# FAB_FTDI.net
KiCad netlist of a schematic drawn in EAGLE
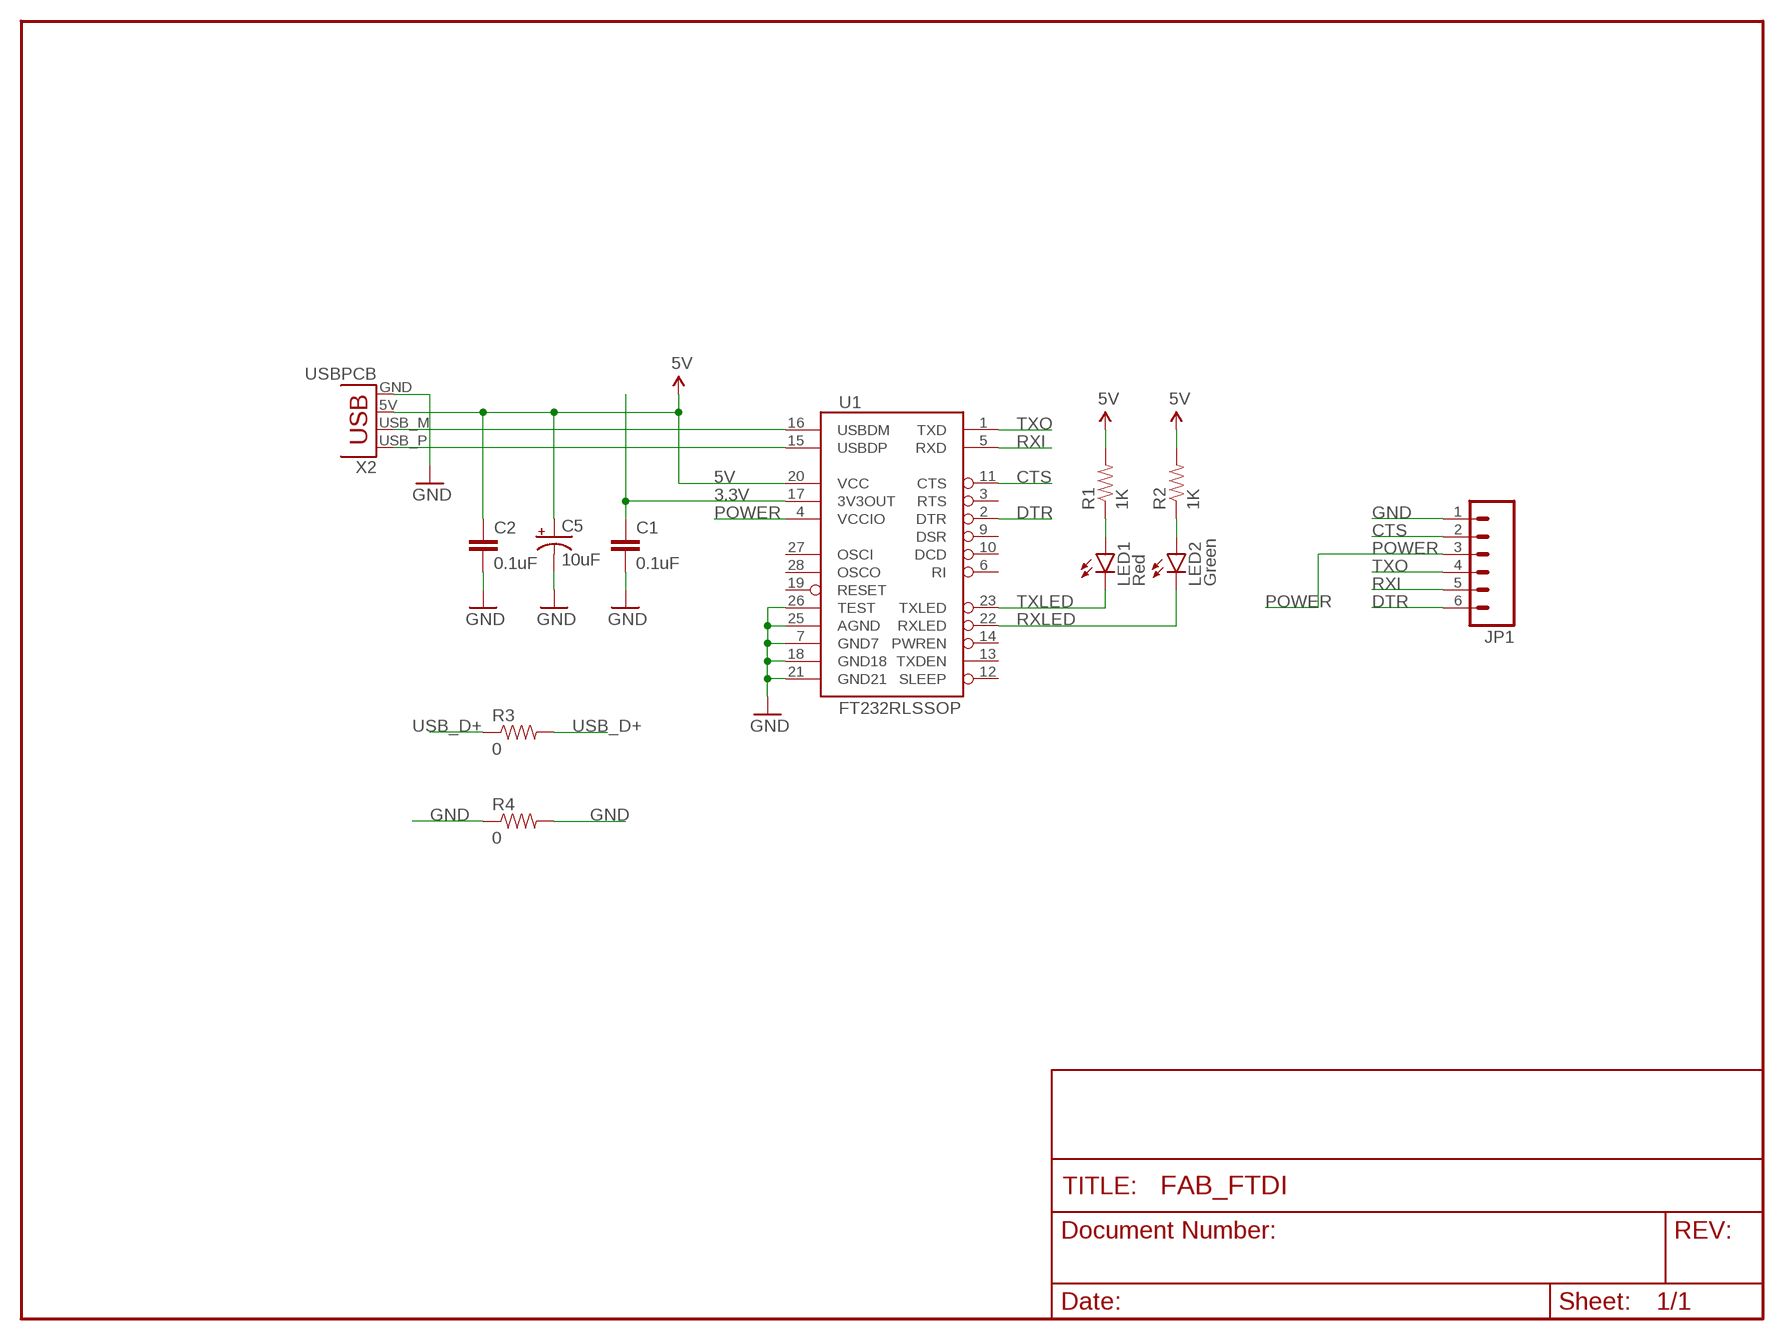
[diagram p0: schematic, sheet 1]

(export (version "E")
  (design (tool "Eeschema 10.0.6"))
  (components
    (comp (ref "C1")
      (value "0.1uF")
      (footprint "eagle-import:1206")
      (libsource (lib "eagle-import") (part "CAP1206"))
    )
    (comp (ref "C2")
      (value "0.1uF")
      (footprint "eagle-import:1206")
      (libsource (lib "eagle-import") (part "CAP1206"))
    )
    (comp (ref "C5")
      (value "10uF")
      (footprint "eagle-import:EIA3216")
      (libsource (lib "eagle-import") (part "CAP_POL1206"))
    )
    (comp (ref "JP1")
      (value "M06SMD-FEMALE-V2")
      (footprint "eagle-import:1X06-SMD-FEMALE-V2")
      (libsource (lib "eagle-import") (part "M06SMD-FEMALE-V2"))
    )
    (comp (ref "LED1")
      (value "Red")
      (footprint "eagle-import:LED-1206")
      (libsource (lib "eagle-import") (part "LED1206"))
    )
    (comp (ref "LED2")
      (value "Green")
      (footprint "eagle-import:LED-1206")
      (libsource (lib "eagle-import") (part "LED1206"))
    )
    (comp (ref "R1")
      (value "1K")
      (footprint "eagle-import:1206")
      (libsource (lib "eagle-import") (part "RESISTOR1206"))
    )
    (comp (ref "R2")
      (value "1K")
      (footprint "eagle-import:1206")
      (libsource (lib "eagle-import") (part "RESISTOR1206"))
    )
    (comp (ref "R3")
      (value "0")
      (footprint "eagle-import:1206")
      (libsource (lib "eagle-import") (part "RESISTOR1206"))
    )
    (comp (ref "R4")
      (value "0")
      (footprint "eagle-import:1206")
      (libsource (lib "eagle-import") (part "RESISTOR1206"))
    )
    (comp (ref "U1")
      (value "FT232RLSSOP")
      (footprint "eagle-import:SSOP28DB")
      (libsource (lib "eagle-import") (part "FT232RLSSOP"))
    )
    (comp (ref "X2")
      (value "USBPCB")
      (footprint "eagle-import:USB-A-PCB")
      (libsource (lib "eagle-import") (part "USBPCB"))
    )
  )
  (nets
    (net (code "1") (name "/3.3V") (class "Default")
      (node (ref "C1") (pin "1") (pinfunction "1_1") (pintype "passive"))
      (node (ref "U1") (pin "17") (pinfunction "3V3OUT_17") (pintype "output"))
    )
    (net (code "2") (name "/CTS") (class "Default")
      (node (ref "JP1") (pin "2") (pinfunction "2_2") (pintype "passive"))
      (node (ref "U1") (pin "11") (pinfunction "CTS_11") (pintype "input"))
    )
    (net (code "3") (name "/DTR") (class "Default")
      (node (ref "JP1") (pin "6") (pinfunction "6_6") (pintype "passive"))
      (node (ref "U1") (pin "2") (pinfunction "DTR_2") (pintype "output"))
    )
    (net (code "4") (name "/POWER") (class "Default")
      (node (ref "JP1") (pin "3") (pinfunction "3_3") (pintype "passive"))
      (node (ref "U1") (pin "4") (pinfunction "VCCIO_4") (pintype "power_in"))
    )
    (net (code "5") (name "/RXI") (class "Default")
      (node (ref "JP1") (pin "5") (pinfunction "5_5") (pintype "passive"))
      (node (ref "U1") (pin "5") (pinfunction "RXD_5") (pintype "input"))
    )
    (net (code "6") (name "/RXLED") (class "Default")
      (node (ref "LED2") (pin "C") (pinfunction "C_C") (pintype "passive"))
      (node (ref "U1") (pin "22") (pinfunction "RXLED_22") (pintype "input"))
    )
    (net (code "7") (name "/TXLED") (class "Default")
      (node (ref "LED1") (pin "C") (pinfunction "C_C") (pintype "passive"))
      (node (ref "U1") (pin "23") (pinfunction "TXLED_23") (pintype "input"))
    )
    (net (code "8") (name "/TXO") (class "Default")
      (node (ref "JP1") (pin "4") (pinfunction "4_4") (pintype "passive"))
      (node (ref "U1") (pin "1") (pinfunction "TXD_1") (pintype "output"))
    )
    (net (code "9") (name "/USB_D+") (class "Default")
      (node (ref "R3") (pin "1") (pinfunction "1_1") (pintype "passive"))
      (node (ref "R3") (pin "2") (pinfunction "2_2") (pintype "passive"))
      (node (ref "U1") (pin "15") (pinfunction "USBDP_15") (pintype "bidirectional"))
      (node (ref "X2") (pin "USB_P") (pinfunction "D+_USB_P") (pintype "bidirectional"))
    )
    (net (code "10") (name "5V") (class "Default")
      (node (ref "C2") (pin "1") (pinfunction "1_1") (pintype "passive"))
      (node (ref "C5") (pin "A") (pinfunction "+_A") (pintype "passive"))
      (node (ref "R1") (pin "2") (pinfunction "2_2") (pintype "passive"))
      (node (ref "R2") (pin "2") (pinfunction "2_2") (pintype "passive"))
      (node (ref "U1") (pin "20") (pinfunction "VCC_20") (pintype "power_in"))
      (node (ref "X2") (pin "5V") (pinfunction "VBUS_5V") (pintype "bidirectional"))
    )
    (net (code "11") (name "GND") (class "Default")
      (node (ref "C1") (pin "2") (pinfunction "2_2") (pintype "passive"))
      (node (ref "C2") (pin "2") (pinfunction "2_2") (pintype "passive"))
      (node (ref "C5") (pin "C") (pinfunction "-_C") (pintype "passive"))
      (node (ref "JP1") (pin "1") (pinfunction "1_1") (pintype "passive"))
      (node (ref "R4") (pin "1") (pinfunction "1_1") (pintype "passive"))
      (node (ref "R4") (pin "2") (pinfunction "2_2") (pintype "passive"))
      (node (ref "U1") (pin "18") (pinfunction "GND18_18") (pintype "power_in"))
      (node (ref "U1") (pin "21") (pinfunction "GND21_21") (pintype "power_in"))
      (node (ref "U1") (pin "25") (pinfunction "AGND_25") (pintype "power_in"))
      (node (ref "U1") (pin "26") (pinfunction "TEST_26") (pintype "input"))
      (node (ref "U1") (pin "7") (pinfunction "GND7_7") (pintype "power_in"))
      (node (ref "X2") (pin "GND") (pinfunction "GND_GND") (pintype "bidirectional"))
    )
    (net (code "12") (name "Net-(LED1-PadA)") (class "Default")
      (node (ref "LED1") (pin "A") (pinfunction "A_A") (pintype "passive"))
      (node (ref "R1") (pin "1") (pinfunction "1_1") (pintype "passive"))
    )
    (net (code "13") (name "Net-(LED2-PadA)") (class "Default")
      (node (ref "LED2") (pin "A") (pinfunction "A_A") (pintype "passive"))
      (node (ref "R2") (pin "1") (pinfunction "1_1") (pintype "passive"))
    )
    (net (code "14") (name "Net-(U1-USBDM)") (class "Default")
      (node (ref "U1") (pin "16") (pinfunction "USBDM_16") (pintype "bidirectional"))
      (node (ref "X2") (pin "USB_M") (pinfunction "D-_USB_M") (pintype "bidirectional"))
    )
    (net (code "15") (name "unconnected-(U1-DCD-Pad10)") (class "Default")
      (node (ref "U1") (pin "10") (pinfunction "DCD_10") (pintype "input"))
    )
    (net (code "16") (name "unconnected-(U1-DSR-Pad9)") (class "Default")
      (node (ref "U1") (pin "9") (pinfunction "DSR_9") (pintype "input"))
    )
    (net (code "17") (name "unconnected-(U1-OSCI-Pad27)") (class "Default")
      (node (ref "U1") (pin "27") (pinfunction "OSCI_27") (pintype "input"))
    )
    (net (code "18") (name "unconnected-(U1-OSCO-Pad28)") (class "Default")
      (node (ref "U1") (pin "28") (pinfunction "OSCO_28") (pintype "output"))
    )
    (net (code "19") (name "unconnected-(U1-PWREN-Pad14)") (class "Default")
      (node (ref "U1") (pin "14") (pinfunction "PWREN_14") (pintype "input"))
    )
    (net (code "20") (name "unconnected-(U1-RESET-Pad19)") (class "Default")
      (node (ref "U1") (pin "19") (pinfunction "RESET_19") (pintype "input"))
    )
    (net (code "21") (name "unconnected-(U1-RI-Pad6)") (class "Default")
      (node (ref "U1") (pin "6") (pinfunction "RI_6") (pintype "input"))
    )
    (net (code "22") (name "unconnected-(U1-RTS-Pad3)") (class "Default")
      (node (ref "U1") (pin "3") (pinfunction "RTS_3") (pintype "output"))
    )
    (net (code "23") (name "unconnected-(U1-SLEEP-Pad12)") (class "Default")
      (node (ref "U1") (pin "12") (pinfunction "SLEEP_12") (pintype "input"))
    )
    (net (code "24") (name "unconnected-(U1-TXDEN-Pad13)") (class "Default")
      (node (ref "U1") (pin "13") (pinfunction "TXDEN_13") (pintype "input"))
    )
  )
)
